# RS232_NPN_PNP_Negative_FTDI.net
KiCad netlist of a schematic drawn in EAGLE
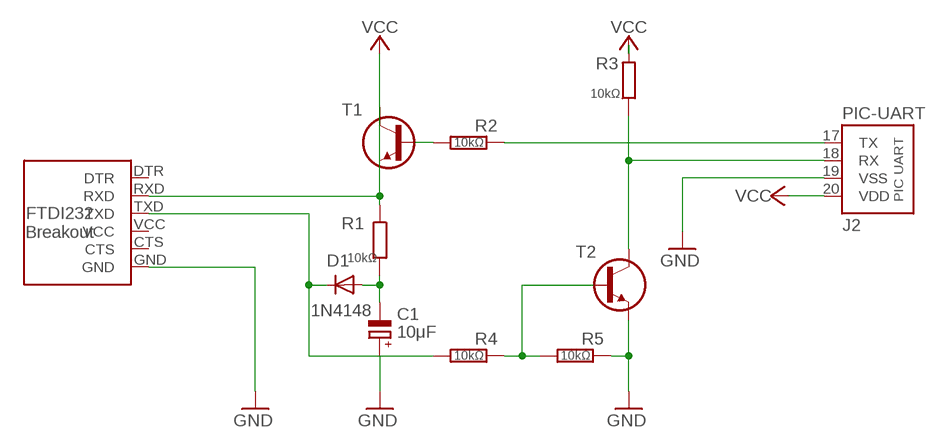
[diagram p0: schematic, sheet 1]

(export (version "E")
  (design (tool "Eeschema 10.0.6"))
  (components
    (comp (ref "C1")
      (value "10μF")
      (footprint "eagle-import:E2,5-5_V")
      (libsource (lib "eagle-import") (part "CPOLE2,5-5/V"))
    )
    (comp (ref "D1")
      (value "1N4148")
      (footprint "eagle-import:DO34-5V")
      (libsource (lib "eagle-import") (part "1N414834-5V"))
    )
    (comp (ref "J1")
      (value "FTDI232-BO")
      (footprint "eagle-import:FTDI232-BO")
      (libsource (lib "eagle-import") (part "FTDI232-BO"))
    )
    (comp (ref "J2")
      (value "PIC-UART")
      (footprint "eagle-import:PIC-UART")
      (libsource (lib "eagle-import") (part "PIC-UART"))
    )
    (comp (ref "R1")
      (value "10kΩ")
      (footprint "eagle-import:0202_5-V")
      (libsource (lib "eagle-import") (part "R0202/5-V"))
    )
    (comp (ref "R2")
      (value "10kΩ")
      (footprint "eagle-import:0202_10-V")
      (libsource (lib "eagle-import") (part "R0202/10-V"))
    )
    (comp (ref "R3")
      (value "10kΩ")
      (footprint "eagle-import:0202_7-V")
      (libsource (lib "eagle-import") (part "R0202/7-V"))
    )
    (comp (ref "R4")
      (value "10kΩ")
      (footprint "eagle-import:0202_7")
      (libsource (lib "eagle-import") (part "R0202/7"))
    )
    (comp (ref "R5")
      (value "10kΩ")
      (footprint "eagle-import:0202_2V")
      (libsource (lib "eagle-import") (part "R0202/2V"))
    )
    (comp (ref "T1")
      (value "BC547CBE")
      (footprint "eagle-import:TO92-CBE")
      (libsource (lib "eagle-import") (part "BC547CBE"))
    )
    (comp (ref "T2")
      (value "BC547CBE")
      (footprint "eagle-import:TO92-CBE")
      (libsource (lib "eagle-import") (part "BC547CBE"))
    )
  )
  (nets
    (net (code "1") (name "GND") (class "Default")
      (node (ref "C1") (pin "+") (pinfunction "+_+") (pintype "passive"))
      (node (ref "J1") (pin "GND") (pinfunction "GND_GND") (pintype "bidirectional"))
      (node (ref "J2") (pin "19") (pinfunction "VSS_19") (pintype "passive"))
      (node (ref "R5") (pin "1") (pinfunction "1_1") (pintype "passive"))
      (node (ref "T2") (pin "E") (pinfunction "E_E") (pintype "passive"))
    )
    (net (code "2") (name "Net-(C1-Pad-)") (class "Default")
      (node (ref "C1") (pin "-") (pinfunction "-_-") (pintype "passive"))
      (node (ref "D1") (pin "A") (pinfunction "A_A") (pintype "passive"))
      (node (ref "R1") (pin "2") (pinfunction "2_2") (pintype "passive"))
    )
    (net (code "3") (name "Net-(D1-PadC)") (class "Default")
      (node (ref "D1") (pin "C") (pinfunction "C_C") (pintype "passive"))
      (node (ref "J1") (pin "TXD") (pinfunction "TXD_TXD") (pintype "bidirectional"))
      (node (ref "R4") (pin "2") (pinfunction "2_2") (pintype "passive"))
    )
    (net (code "4") (name "Net-(J1-PadRXD)") (class "Default")
      (node (ref "J1") (pin "RXD") (pinfunction "RXD_RXD") (pintype "bidirectional"))
      (node (ref "R1") (pin "1") (pinfunction "1_1") (pintype "passive"))
      (node (ref "T1") (pin "C") (pinfunction "C_C") (pintype "passive"))
    )
    (net (code "5") (name "Net-(J2-RX)") (class "Default")
      (node (ref "J2") (pin "18") (pinfunction "RX_18") (pintype "passive"))
      (node (ref "R3") (pin "1") (pinfunction "1_1") (pintype "passive"))
      (node (ref "T2") (pin "C") (pinfunction "C_C") (pintype "passive"))
    )
    (net (code "6") (name "Net-(J2-TX)") (class "Default")
      (node (ref "J2") (pin "17") (pinfunction "TX_17") (pintype "passive"))
      (node (ref "R2") (pin "1") (pinfunction "1_1") (pintype "passive"))
    )
    (net (code "7") (name "Net-(R2-Pad2)") (class "Default")
      (node (ref "R2") (pin "2") (pinfunction "2_2") (pintype "passive"))
      (node (ref "T1") (pin "B") (pinfunction "B_B") (pintype "passive"))
    )
    (net (code "8") (name "Net-(R4-Pad1)") (class "Default")
      (node (ref "R4") (pin "1") (pinfunction "1_1") (pintype "passive"))
      (node (ref "R5") (pin "2") (pinfunction "2_2") (pintype "passive"))
      (node (ref "T2") (pin "B") (pinfunction "B_B") (pintype "passive"))
    )
    (net (code "9") (name "VCC") (class "Default")
      (node (ref "J2") (pin "20") (pinfunction "VDD_20") (pintype "passive"))
      (node (ref "R3") (pin "2") (pinfunction "2_2") (pintype "passive"))
      (node (ref "T1") (pin "E") (pinfunction "E_E") (pintype "passive"))
    )
    (net (code "10") (name "unconnected-(J1-PadCTS)") (class "Default")
      (node (ref "J1") (pin "CTS") (pinfunction "CTS_CTS") (pintype "bidirectional"))
    )
    (net (code "11") (name "unconnected-(J1-PadDTR)") (class "Default")
      (node (ref "J1") (pin "DTR") (pinfunction "DTR_DTR") (pintype "bidirectional"))
    )
    (net (code "12") (name "unconnected-(J1-PadVCC)") (class "Default")
      (node (ref "J1") (pin "VCC") (pinfunction "VCC_VCC") (pintype "bidirectional"))
    )
  )
)
